# SCH_PCB-micropad_2024-07-05.net
KiCad netlist of a schematic drawn in EasyEDA
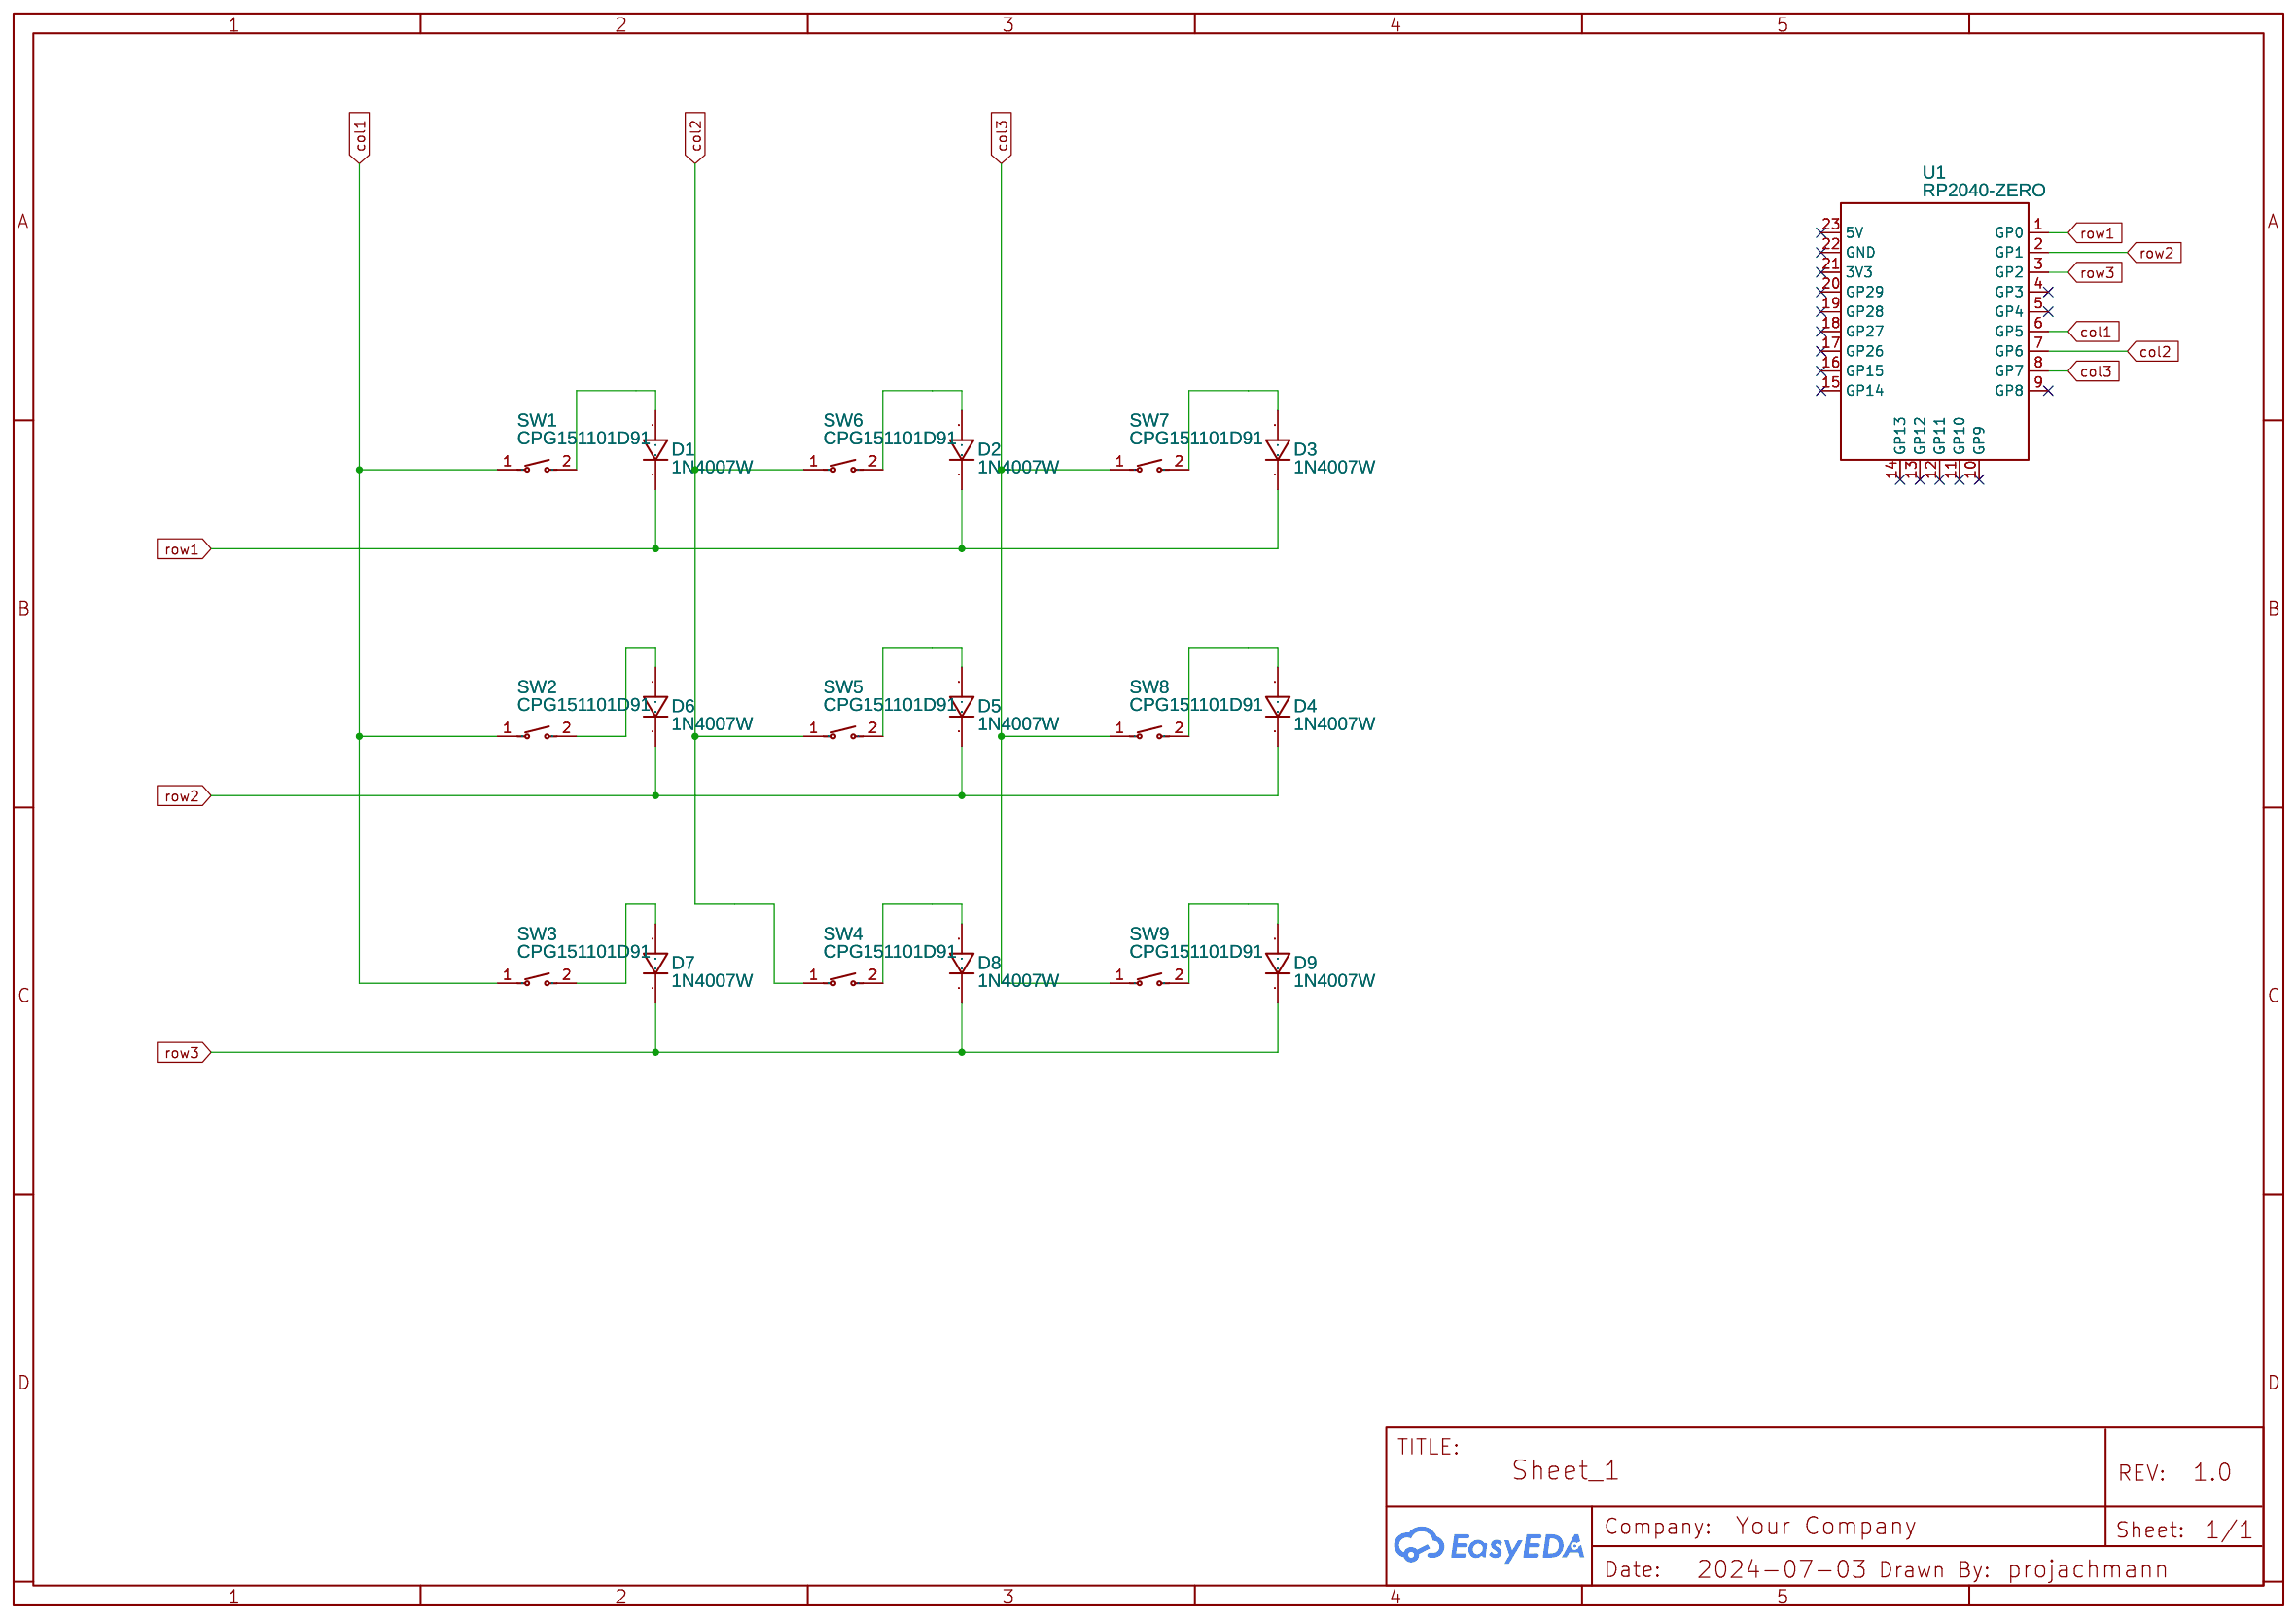
[diagram p0: schematic sheet]

(export (version "E")
  (design (tool "Eeschema 10.0.6"))
  (components
    (comp (ref "D1")
      (value "1N4007W")
      (fields (field (name "Manufacturer") "BLUE ROCKET"))
      (libsource (lib "") (part "1N4007W"))
    )
    (comp (ref "D2")
      (value "1N4007W")
      (fields (field (name "Manufacturer") "BLUE ROCKET"))
      (libsource (lib "") (part "1N4007W"))
    )
    (comp (ref "D3")
      (value "1N4007W")
      (fields (field (name "Manufacturer") "BLUE ROCKET"))
      (libsource (lib "") (part "1N4007W"))
    )
    (comp (ref "D4")
      (value "1N4007W")
      (fields (field (name "Manufacturer") "BLUE ROCKET"))
      (libsource (lib "") (part "1N4007W"))
    )
    (comp (ref "D5")
      (value "1N4007W")
      (fields (field (name "Manufacturer") "BLUE ROCKET"))
      (libsource (lib "") (part "1N4007W"))
    )
    (comp (ref "D6")
      (value "1N4007W")
      (fields (field (name "Manufacturer") "BLUE ROCKET"))
      (libsource (lib "") (part "1N4007W"))
    )
    (comp (ref "D7")
      (value "1N4007W")
      (fields (field (name "Manufacturer") "BLUE ROCKET"))
      (libsource (lib "") (part "1N4007W"))
    )
    (comp (ref "D8")
      (value "1N4007W")
      (fields (field (name "Manufacturer") "BLUE ROCKET"))
      (libsource (lib "") (part "1N4007W"))
    )
    (comp (ref "D9")
      (value "1N4007W")
      (fields (field (name "Manufacturer") "BLUE ROCKET"))
      (libsource (lib "") (part "1N4007W"))
    )
    (comp (ref "SW1")
      (value "CPG151101D91")
      (fields (field (name "Manufacturer") "Kailh(凯华)"))
      (libsource (lib "") (part "CPG151101D91"))
    )
    (comp (ref "SW2")
      (value "CPG151101D91")
      (fields (field (name "Manufacturer") "Kailh(凯华)"))
      (libsource (lib "") (part "CPG151101D91"))
    )
    (comp (ref "SW3")
      (value "CPG151101D91")
      (fields (field (name "Manufacturer") "Kailh(凯华)"))
      (libsource (lib "") (part "CPG151101D91"))
    )
    (comp (ref "SW4")
      (value "CPG151101D91")
      (fields (field (name "Manufacturer") "Kailh(凯华)"))
      (libsource (lib "") (part "CPG151101D91"))
    )
    (comp (ref "SW5")
      (value "CPG151101D91")
      (fields (field (name "Manufacturer") "Kailh(凯华)"))
      (libsource (lib "") (part "CPG151101D91"))
    )
    (comp (ref "SW6")
      (value "CPG151101D91")
      (fields (field (name "Manufacturer") "Kailh(凯华)"))
      (libsource (lib "") (part "CPG151101D91"))
    )
    (comp (ref "SW7")
      (value "CPG151101D91")
      (fields (field (name "Manufacturer") "Kailh(凯华)"))
      (libsource (lib "") (part "CPG151101D91"))
    )
    (comp (ref "SW8")
      (value "CPG151101D91")
      (fields (field (name "Manufacturer") "Kailh(凯华)"))
      (libsource (lib "") (part "CPG151101D91"))
    )
    (comp (ref "SW9")
      (value "CPG151101D91")
      (fields (field (name "Manufacturer") "Kailh(凯华)"))
      (libsource (lib "") (part "CPG151101D91"))
    )
    (comp (ref "U1")
      (value "RP2040-ZERO")
      (fields
        (field (name "Manufacturer Part") "RP2040-Zero")
        (field (name "Manufacturer") "Waveshare(微雪电子)")
      )
      (libsource (lib "") (part "RP2040-ZERO"))
    )
  )
  (nets
    (net (code "1") (name "Net-(D1-Pad2)") (class "Default")
      (node (ref "D1") (pin "2") (pinfunction "2_2") (pintype "unspecified"))
      (node (ref "SW1") (pin "2") (pinfunction "2_2") (pintype "unspecified"))
    )
    (net (code "2") (name "Net-(D2-Pad2)") (class "Default")
      (node (ref "D2") (pin "2") (pinfunction "2_2") (pintype "unspecified"))
      (node (ref "SW6") (pin "2") (pinfunction "2_2") (pintype "unspecified"))
    )
    (net (code "3") (name "Net-(D3-Pad2)") (class "Default")
      (node (ref "D3") (pin "2") (pinfunction "2_2") (pintype "unspecified"))
      (node (ref "SW7") (pin "2") (pinfunction "2_2") (pintype "unspecified"))
    )
    (net (code "4") (name "Net-(D4-Pad2)") (class "Default")
      (node (ref "D4") (pin "2") (pinfunction "2_2") (pintype "unspecified"))
      (node (ref "SW8") (pin "2") (pinfunction "2_2") (pintype "unspecified"))
    )
    (net (code "5") (name "Net-(D5-Pad2)") (class "Default")
      (node (ref "D5") (pin "2") (pinfunction "2_2") (pintype "unspecified"))
      (node (ref "SW5") (pin "2") (pinfunction "2_2") (pintype "unspecified"))
    )
    (net (code "6") (name "Net-(D6-Pad2)") (class "Default")
      (node (ref "D6") (pin "2") (pinfunction "2_2") (pintype "unspecified"))
      (node (ref "SW2") (pin "2") (pinfunction "2_2") (pintype "unspecified"))
    )
    (net (code "7") (name "Net-(D7-Pad2)") (class "Default")
      (node (ref "D7") (pin "2") (pinfunction "2_2") (pintype "unspecified"))
      (node (ref "SW3") (pin "2") (pinfunction "2_2") (pintype "unspecified"))
    )
    (net (code "8") (name "Net-(D8-Pad2)") (class "Default")
      (node (ref "D8") (pin "2") (pinfunction "2_2") (pintype "unspecified"))
      (node (ref "SW4") (pin "2") (pinfunction "2_2") (pintype "unspecified"))
    )
    (net (code "9") (name "Net-(D9-Pad2)") (class "Default")
      (node (ref "D9") (pin "2") (pinfunction "2_2") (pintype "unspecified"))
      (node (ref "SW9") (pin "2") (pinfunction "2_2") (pintype "unspecified"))
    )
    (net (code "10") (name "col1") (class "Default")
      (node (ref "SW1") (pin "1") (pinfunction "1_1") (pintype "unspecified"))
      (node (ref "SW2") (pin "1") (pinfunction "1_1") (pintype "unspecified"))
      (node (ref "SW3") (pin "1") (pinfunction "1_1") (pintype "unspecified"))
      (node (ref "U1") (pin "6") (pinfunction "GP5_6") (pintype "unspecified"))
    )
    (net (code "11") (name "col2") (class "Default")
      (node (ref "SW4") (pin "1") (pinfunction "1_1") (pintype "unspecified"))
      (node (ref "SW5") (pin "1") (pinfunction "1_1") (pintype "unspecified"))
      (node (ref "SW6") (pin "1") (pinfunction "1_1") (pintype "unspecified"))
      (node (ref "U1") (pin "7") (pinfunction "GP6_7") (pintype "unspecified"))
    )
    (net (code "12") (name "col3") (class "Default")
      (node (ref "SW7") (pin "1") (pinfunction "1_1") (pintype "unspecified"))
      (node (ref "SW8") (pin "1") (pinfunction "1_1") (pintype "unspecified"))
      (node (ref "SW9") (pin "1") (pinfunction "1_1") (pintype "unspecified"))
      (node (ref "U1") (pin "8") (pinfunction "GP7_8") (pintype "unspecified"))
    )
    (net (code "13") (name "row1") (class "Default")
      (node (ref "D1") (pin "1") (pinfunction "1_1") (pintype "unspecified"))
      (node (ref "D2") (pin "1") (pinfunction "1_1") (pintype "unspecified"))
      (node (ref "D3") (pin "1") (pinfunction "1_1") (pintype "unspecified"))
      (node (ref "U1") (pin "1") (pinfunction "GP0_1") (pintype "unspecified"))
    )
    (net (code "14") (name "row2") (class "Default")
      (node (ref "D4") (pin "1") (pinfunction "1_1") (pintype "unspecified"))
      (node (ref "D5") (pin "1") (pinfunction "1_1") (pintype "unspecified"))
      (node (ref "D6") (pin "1") (pinfunction "1_1") (pintype "unspecified"))
      (node (ref "U1") (pin "2") (pinfunction "GP1_2") (pintype "unspecified"))
    )
    (net (code "15") (name "row3") (class "Default")
      (node (ref "D7") (pin "1") (pinfunction "1_1") (pintype "unspecified"))
      (node (ref "D8") (pin "1") (pinfunction "1_1") (pintype "unspecified"))
      (node (ref "D9") (pin "1") (pinfunction "1_1") (pintype "unspecified"))
      (node (ref "U1") (pin "3") (pinfunction "GP2_3") (pintype "unspecified"))
    )
    (net (code "16") (name "unconnected-(U1-3V3-Pad21)") (class "Default")
      (node (ref "U1") (pin "21") (pinfunction "3V3_21") (pintype "unspecified+no_connect"))
    )
    (net (code "17") (name "unconnected-(U1-5V-Pad23)") (class "Default")
      (node (ref "U1") (pin "23") (pinfunction "5V_23") (pintype "unspecified+no_connect"))
    )
    (net (code "18") (name "unconnected-(U1-GND-Pad22)") (class "Default")
      (node (ref "U1") (pin "22") (pinfunction "GND_22") (pintype "unspecified+no_connect"))
    )
    (net (code "19") (name "unconnected-(U1-GP3-Pad4)") (class "Default")
      (node (ref "U1") (pin "4") (pinfunction "GP3_4") (pintype "unspecified+no_connect"))
    )
    (net (code "20") (name "unconnected-(U1-GP4-Pad5)") (class "Default")
      (node (ref "U1") (pin "5") (pinfunction "GP4_5") (pintype "unspecified+no_connect"))
    )
    (net (code "21") (name "unconnected-(U1-GP8-Pad9)") (class "Default")
      (node (ref "U1") (pin "9") (pinfunction "GP8_9") (pintype "unspecified+no_connect"))
    )
    (net (code "22") (name "unconnected-(U1-GP9-Pad10)") (class "Default")
      (node (ref "U1") (pin "10") (pinfunction "GP9_10") (pintype "unspecified+no_connect"))
    )
    (net (code "23") (name "unconnected-(U1-GP10-Pad11)") (class "Default")
      (node (ref "U1") (pin "11") (pinfunction "GP10_11") (pintype "unspecified+no_connect"))
    )
    (net (code "24") (name "unconnected-(U1-GP11-Pad12)") (class "Default")
      (node (ref "U1") (pin "12") (pinfunction "GP11_12") (pintype "unspecified+no_connect"))
    )
    (net (code "25") (name "unconnected-(U1-GP12-Pad13)") (class "Default")
      (node (ref "U1") (pin "13") (pinfunction "GP12_13") (pintype "unspecified+no_connect"))
    )
    (net (code "26") (name "unconnected-(U1-GP13-Pad14)") (class "Default")
      (node (ref "U1") (pin "14") (pinfunction "GP13_14") (pintype "unspecified+no_connect"))
    )
    (net (code "27") (name "unconnected-(U1-GP14-Pad15)") (class "Default")
      (node (ref "U1") (pin "15") (pinfunction "GP14_15") (pintype "unspecified+no_connect"))
    )
    (net (code "28") (name "unconnected-(U1-GP15-Pad16)") (class "Default")
      (node (ref "U1") (pin "16") (pinfunction "GP15_16") (pintype "unspecified+no_connect"))
    )
    (net (code "29") (name "unconnected-(U1-GP26-Pad17)") (class "Default")
      (node (ref "U1") (pin "17") (pinfunction "GP26_17") (pintype "unspecified+no_connect"))
    )
    (net (code "30") (name "unconnected-(U1-GP27-Pad18)") (class "Default")
      (node (ref "U1") (pin "18") (pinfunction "GP27_18") (pintype "unspecified+no_connect"))
    )
    (net (code "31") (name "unconnected-(U1-GP28-Pad19)") (class "Default")
      (node (ref "U1") (pin "19") (pinfunction "GP28_19") (pintype "unspecified+no_connect"))
    )
    (net (code "32") (name "unconnected-(U1-GP29-Pad20)") (class "Default")
      (node (ref "U1") (pin "20") (pinfunction "GP29_20") (pintype "unspecified+no_connect"))
    )
  )
)
